# rf_swrmet.net
KiCad netlist of a schematic drawn in Altium Designer
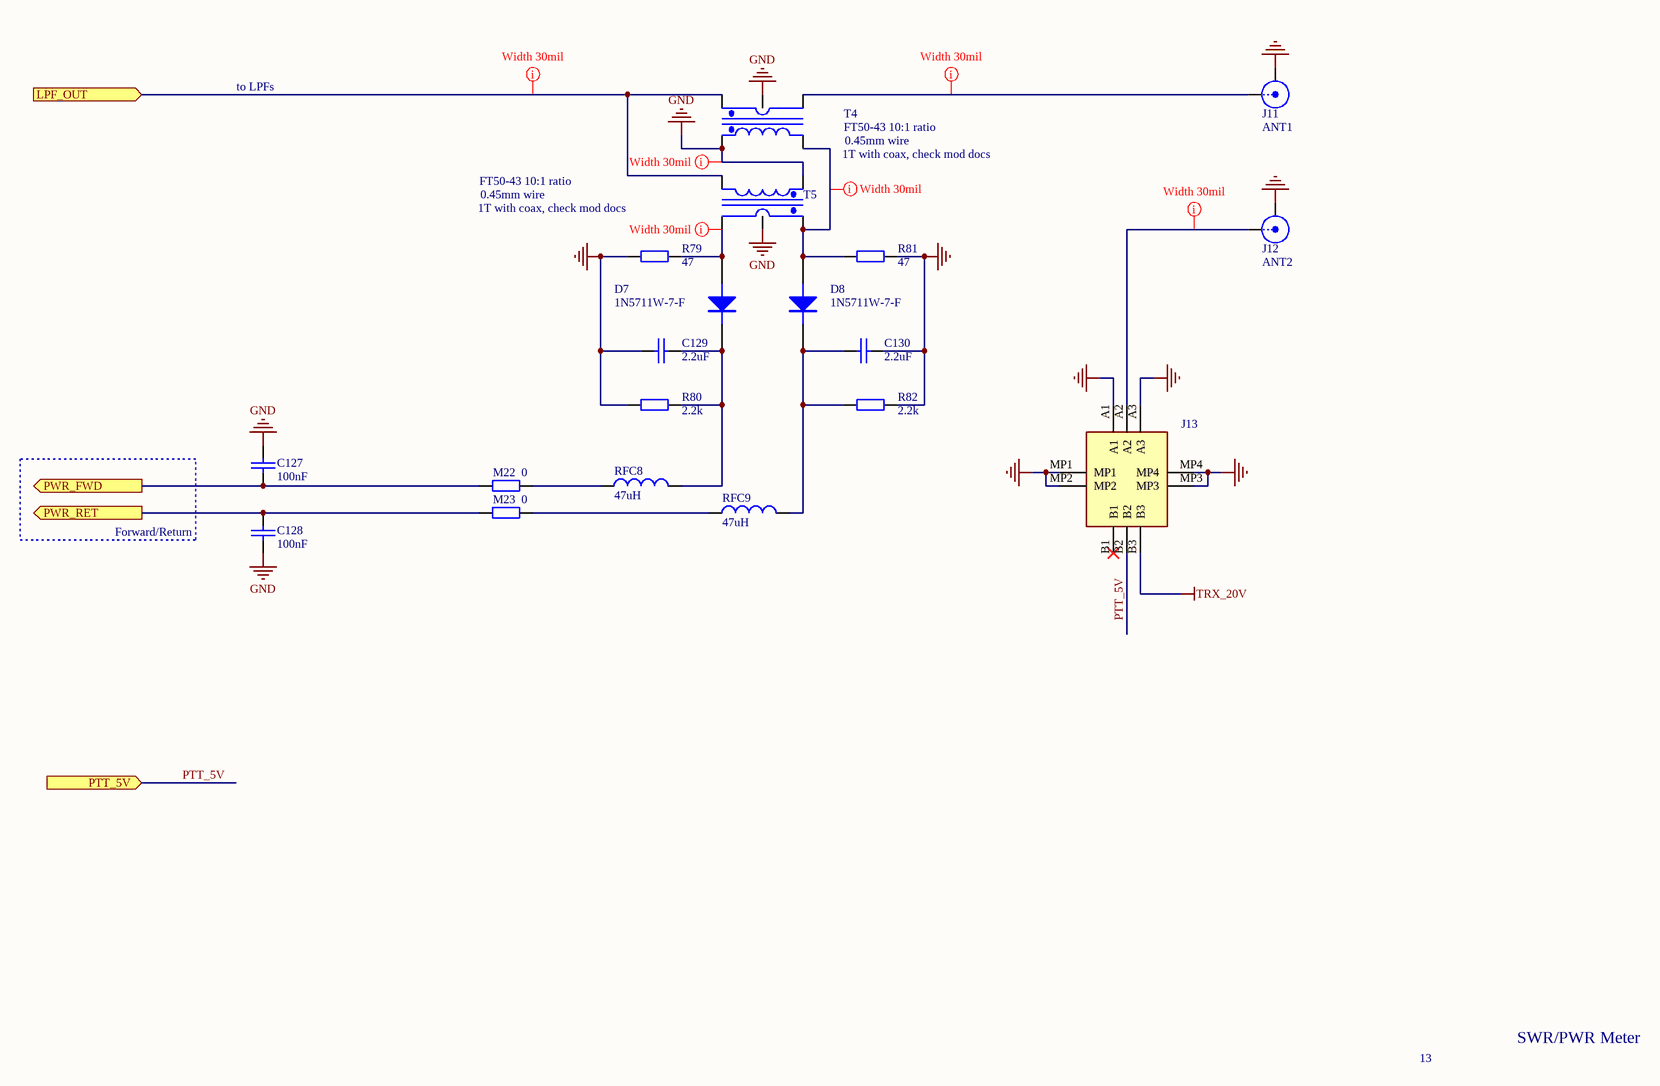
[diagram p0: rf_swrmet.SchDoc]

(export (version "E")
  (design (tool "Eeschema 10.0.6"))
  (components
    (comp (ref "C127")
      (value "100nF")
      (footprint "0805")
      (description "Capacitor")
      (libsource (lib "mcHF_rf") (part "CAP"))
    )
    (comp (ref "C128")
      (value "100nF")
      (footprint "0805")
      (description "Capacitor")
      (libsource (lib "mcHF_rf") (part "CAP"))
    )
    (comp (ref "C129")
      (value "2.2uF")
      (footprint "0805")
      (description "Capacitor")
      (libsource (lib "mcHF_rf") (part "CAP"))
    )
    (comp (ref "C130")
      (value "2.2uF")
      (footprint "0805")
      (description "Capacitor")
      (libsource (lib "mcHF_rf") (part "CAP"))
    )
    (comp (ref "D7")
      (value "1N5711W-7-F")
      (footprint "SOD87")
      (description "RF DIODE SCHOTTKY 70V, SOD-123F")
      (libsource (lib "mcHF_rf") (part "PMEG6010CEH"))
    )
    (comp (ref "D8")
      (value "1N5711W-7-F")
      (footprint "SOD87")
      (description "RF DIODE SCHOTTKY 70V, SOD-123F")
      (libsource (lib "mcHF_rf") (part "PMEG6010CEH"))
    )
    (comp (ref "J11")
      (value "ANT1")
      (footprint "CON-SMA-RA")
      (description "RF COAXIAL, BNC, JACK")
      (libsource (lib "__rf") (part "BNC"))
    )
    (comp (ref "J12")
      (value "ANT2")
      (footprint "CON-SMA-RA")
      (description "RF COAXIAL, BNC, JACK")
      (libsource (lib "__rf") (part "BNC"))
    )
    (comp (ref "J13")
      (value "1373826")
      (footprint "1373826")
      (fields (field (name "MOUSER PART NUMBER") "651-1373826"))
      (libsource (lib "1373826") (part "1373826"))
    )
    (comp (ref "M22")
      (value "0")
      (footprint "0805")
      (description "Resistor")
      (libsource (lib "") (part "RES_1"))
    )
    (comp (ref "M23")
      (value "0")
      (footprint "0805")
      (description "Resistor")
      (libsource (lib "") (part "RES_1"))
    )
    (comp (ref "R79")
      (value "47")
      (footprint "0805")
      (description "Resistor")
      (libsource (lib "mcHF_rf") (part "RES"))
    )
    (comp (ref "R80")
      (value "2.2k")
      (footprint "0805")
      (description "Resistor")
      (libsource (lib "mcHF_rf") (part "RES"))
    )
    (comp (ref "R81")
      (value "47")
      (footprint "0805")
      (description "Resistor")
      (libsource (lib "mcHF_rf") (part "RES"))
    )
    (comp (ref "R82")
      (value "2.2k")
      (footprint "0805")
      (description "Resistor")
      (libsource (lib "mcHF_rf") (part "RES"))
    )
    (comp (ref "RFC8")
      (value "47uH")
      (footprint "0805")
      (description "INDUCTOR, SIGNAL LINE, 47UH, 1005")
      (libsource (lib "mcHF_rf") (part "TDK-NLV25T"))
    )
    (comp (ref "RFC9")
      (value "47uH")
      (footprint "0805")
      (description "INDUCTOR, SIGNAL LINE, 47UH, 1005")
      (libsource (lib "mcHF_rf") (part "TDK-NLV25T"))
    )
    (comp (ref "T4")
      (value "FT50-43 10:1 ratio")
      (footprint "SWR_TR _new")
      (description "SWR Bridge transformer")
      (libsource (lib "mcHF_rf") (part "SWR_TR"))
    )
    (comp (ref "T5")
      (value "FT50-43 10:1 ratio")
      (footprint "SWR_TR _new")
      (description "SWR Bridge transformer")
      (libsource (lib "mcHF_rf") (part "SWR_TR"))
    )
  )
  (nets
    (net (code "1") (name "/LPF_OUT") (class "Default")
      (node (ref "T4") (pin "3") (pinfunction "Sec+_3") (pintype "passive"))
      (node (ref "T5") (pin "2") (pinfunction "Pri-_2") (pintype "passive"))
    )
    (net (code "2") (name "/PTT_5V") (class "Default")
      (node (ref "J13") (pin "B2") (pinfunction "B2_B2") (pintype "passive"))
    )
    (net (code "3") (name "/PWR_FWD") (class "Default")
      (node (ref "C127") (pin "2") (pinfunction "2_2") (pintype "passive"))
      (node (ref "M22") (pin "2") (pinfunction "2_2") (pintype "passive"))
    )
    (net (code "4") (name "/PWR_RET") (class "Default")
      (node (ref "C128") (pin "1") (pinfunction "1_1") (pintype "passive"))
      (node (ref "M23") (pin "2") (pinfunction "2_2") (pintype "passive"))
    )
    (net (code "5") (name "GND") (class "Default")
      (node (ref "C127") (pin "1") (pinfunction "1_1") (pintype "passive"))
      (node (ref "C128") (pin "2") (pinfunction "2_2") (pintype "passive"))
      (node (ref "C129") (pin "1") (pinfunction "1_1") (pintype "passive"))
      (node (ref "C130") (pin "2") (pinfunction "2_2") (pintype "passive"))
      (node (ref "J11") (pin "2") (pinfunction "Y_2") (pintype "passive"))
      (node (ref "J12") (pin "2") (pinfunction "Y_2") (pintype "passive"))
      (node (ref "J13") (pin "A1") (pinfunction "A1_A1") (pintype "passive"))
      (node (ref "J13") (pin "A3") (pinfunction "A3_A3") (pintype "passive"))
      (node (ref "J13") (pin "MP1") (pinfunction "MP1_MP1") (pintype "passive"))
      (node (ref "J13") (pin "MP2") (pinfunction "MP2_MP2") (pintype "passive"))
      (node (ref "J13") (pin "MP3") (pinfunction "MP3_MP3") (pintype "passive"))
      (node (ref "J13") (pin "MP4") (pinfunction "MP4_MP4") (pintype "passive"))
      (node (ref "R79") (pin "1") (pinfunction "1_1") (pintype "passive"))
      (node (ref "R80") (pin "1") (pinfunction "1_1") (pintype "passive"))
      (node (ref "R81") (pin "2") (pinfunction "2_2") (pintype "passive"))
      (node (ref "R82") (pin "2") (pinfunction "2_2") (pintype "passive"))
      (node (ref "T4") (pin "1") (pinfunction "Pri+_1") (pintype "passive"))
      (node (ref "T4") (pin "5") (pinfunction "Shield_5") (pintype "passive"))
      (node (ref "T5") (pin "1") (pinfunction "Pri+_1") (pintype "passive"))
      (node (ref "T5") (pin "5") (pinfunction "Shield_5") (pintype "passive"))
    )
    (net (code "6") (name "Net-(D7-A)") (class "Default")
      (node (ref "D7") (pin "1") (pinfunction "A_1") (pintype "passive"))
      (node (ref "R79") (pin "2") (pinfunction "2_2") (pintype "passive"))
      (node (ref "T5") (pin "4") (pinfunction "Sec-_4") (pintype "passive"))
    )
    (net (code "7") (name "Net-(D7-K)") (class "Default")
      (node (ref "C129") (pin "2") (pinfunction "2_2") (pintype "passive"))
      (node (ref "D7") (pin "2") (pinfunction "K_2") (pintype "passive"))
      (node (ref "R80") (pin "2") (pinfunction "2_2") (pintype "passive"))
      (node (ref "RFC8") (pin "2") (pinfunction "2_2") (pintype "passive"))
    )
    (net (code "8") (name "Net-(D8-A)") (class "Default")
      (node (ref "D8") (pin "1") (pinfunction "A_1") (pintype "passive"))
      (node (ref "R81") (pin "1") (pinfunction "1_1") (pintype "passive"))
      (node (ref "T4") (pin "2") (pinfunction "Pri-_2") (pintype "passive"))
      (node (ref "T5") (pin "3") (pinfunction "Sec+_3") (pintype "passive"))
    )
    (net (code "9") (name "Net-(D8-K)") (class "Default")
      (node (ref "C130") (pin "1") (pinfunction "1_1") (pintype "passive"))
      (node (ref "D8") (pin "2") (pinfunction "K_2") (pintype "passive"))
      (node (ref "R82") (pin "1") (pinfunction "1_1") (pintype "passive"))
      (node (ref "RFC9") (pin "2") (pinfunction "2_2") (pintype "passive"))
    )
    (net (code "10") (name "Net-(J11-X)") (class "Default")
      (node (ref "J11") (pin "1") (pinfunction "X_1") (pintype "passive"))
      (node (ref "T4") (pin "4") (pinfunction "Sec-_4") (pintype "passive"))
    )
    (net (code "11") (name "Net-(J12-X)") (class "Default")
      (node (ref "J12") (pin "1") (pinfunction "X_1") (pintype "passive"))
      (node (ref "J13") (pin "A2") (pinfunction "A2_A2") (pintype "passive"))
    )
    (net (code "12") (name "Net-(M22-Pad1)") (class "Default")
      (node (ref "M22") (pin "1") (pinfunction "1_1") (pintype "passive"))
      (node (ref "RFC8") (pin "1") (pinfunction "1_1") (pintype "passive"))
    )
    (net (code "13") (name "Net-(M23-Pad1)") (class "Default")
      (node (ref "M23") (pin "1") (pinfunction "1_1") (pintype "passive"))
      (node (ref "RFC9") (pin "1") (pinfunction "1_1") (pintype "passive"))
    )
    (net (code "14") (name "TRX_20V") (class "Default")
      (node (ref "J13") (pin "B3") (pinfunction "B3_B3") (pintype "passive"))
    )
    (net (code "15") (name "unconnected-(J13-PadB1)") (class "Default")
      (node (ref "J13") (pin "B1") (pinfunction "B1_B1") (pintype "passive+no_connect"))
    )
  )
)
